# led-cube.net
KiCad netlist of a schematic drawn in Altium Designer
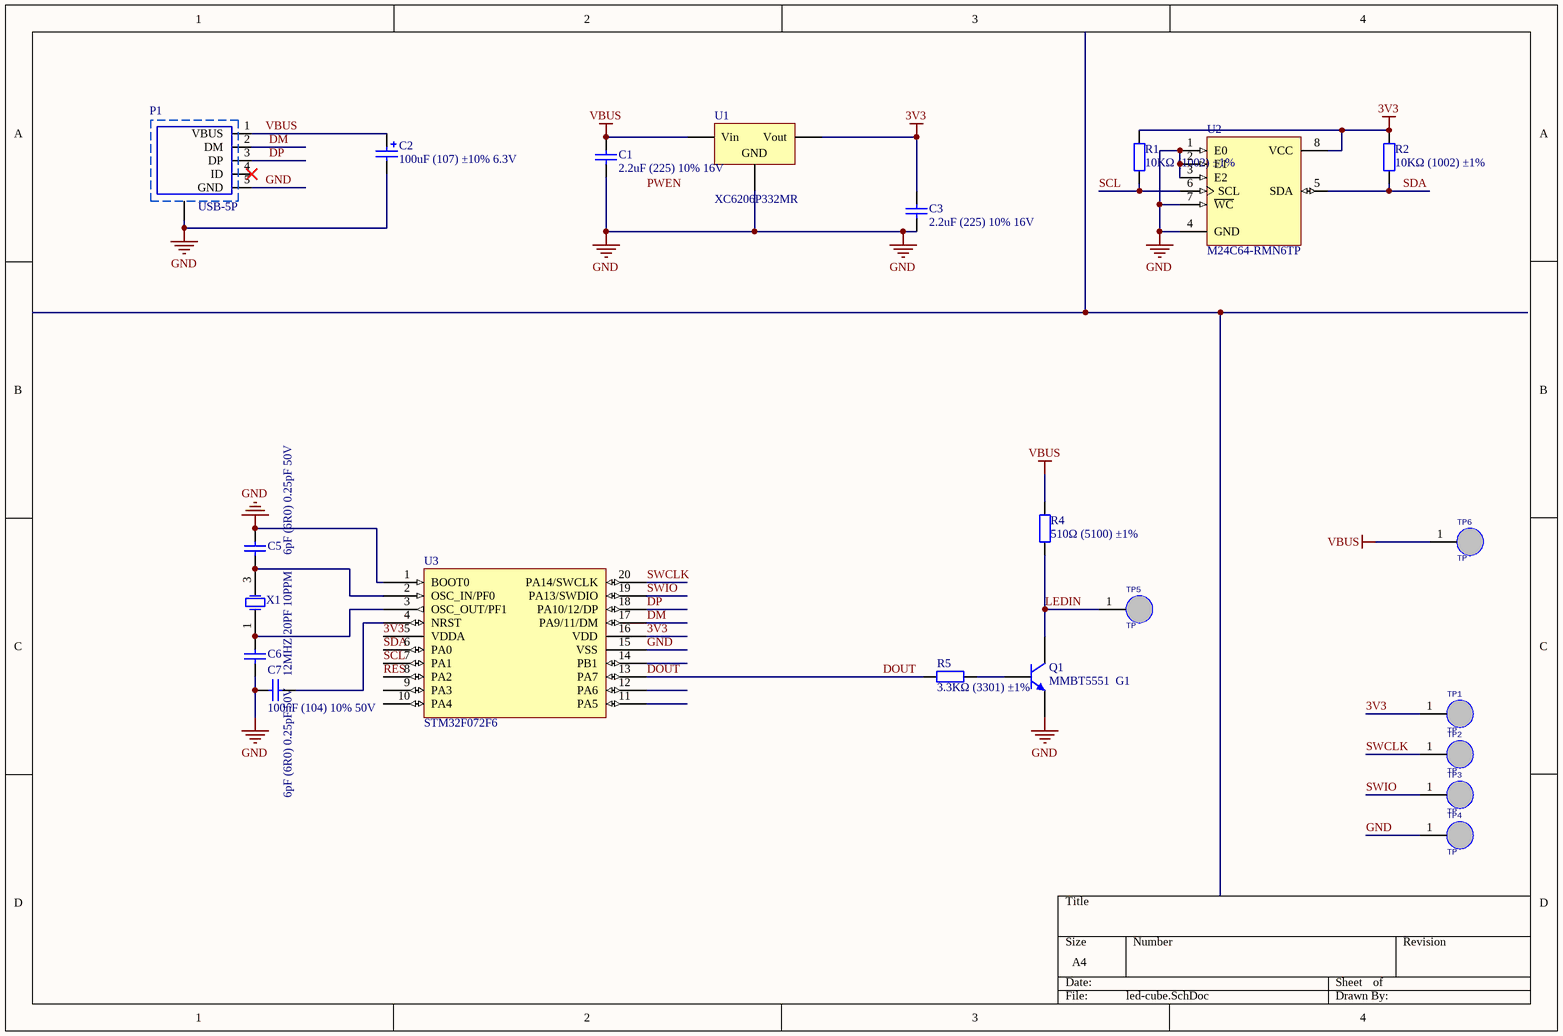
[diagram p0: led-cube.SchDoc]

(export (version "E")
  (design (tool "Eeschema 10.0.6"))
  (components
    (comp (ref "C1")
      (value "2.2uF (225) 10% 16V")
      (footprint "LC-0603_C")
      (description "贴片电容")
      (libsource (lib "Miscellaneous Devices LC") (part "0603 2.2uF (225) 10% 16V"))
    )
    (comp (ref "C2")
      (value "100uF (107) ±10% 6.3V")
      (footprint "LC-CASE-B_3528")
      (description "钽电容")
      (libsource (lib "Miscellaneous Devices LC") (part "3528 100uF (107) 10% 6.3V"))
    )
    (comp (ref "C3")
      (value "2.2uF (225) 10% 16V")
      (footprint "LC-0603_C")
      (description "贴片电容")
      (libsource (lib "Miscellaneous Devices LC") (part "0603 2.2uF (225) 10% 16V"))
    )
    (comp (ref "C5")
      (value "6pF (6R0) 0.25pF 50V")
      (footprint "LC-0603_C")
      (description "贴片电容")
      (libsource (lib "Miscellaneous Devices LC") (part "0603 6pF (6R0) 0.25pF 50V"))
    )
    (comp (ref "C6")
      (value "6pF (6R0) 0.25pF 50V")
      (footprint "LC-0603_C")
      (description "贴片电容")
      (libsource (lib "Miscellaneous Devices LC") (part "0603 6pF (6R0) 0.25pF 50V"))
    )
    (comp (ref "C7")
      (value "100nF (104) 10% 50V")
      (footprint "LC-0603_C")
      (description "贴片电容")
      (libsource (lib "Miscellaneous Devices LC") (part "0603 100nF (104) 10% 50V"))
    )
    (comp (ref "P1") (value "USB-5P") (footprint "USBMICRO-5P") (libsource (lib "tony") (part "USB-5P")))
    (comp (ref "Q1")
      (value "MMBT5551  G1")
      (footprint "LC-SOT-23(SOT-23-3)")
      (description "三极管")
      (libsource (lib "Miscellaneous Devices LC") (part "SOT-23 MMBT5551  G1"))
    )
    (comp (ref "R1")
      (value "10KΩ (1002) ±1%")
      (footprint "LC-0603_R")
      (description "贴片电阻")
      (libsource (lib "Miscellaneous Devices LC") (part "0603 10KΩ (1002) 1%"))
    )
    (comp (ref "R2")
      (value "10KΩ (1002) ±1%")
      (footprint "LC-0603_R")
      (description "贴片电阻")
      (libsource (lib "Miscellaneous Devices LC") (part "0603 10KΩ (1002) 1%"))
    )
    (comp (ref "R4")
      (value "510Ω (5100) ±1%")
      (footprint "LC-0603_R")
      (description "贴片电阻")
      (libsource (lib "Miscellaneous Devices LC") (part "0603 510Ω (5100) 1%"))
    )
    (comp (ref "R5")
      (value "3.3KΩ (3301) ±1%")
      (footprint "LC-0603_R")
      (description "贴片电阻")
      (libsource (lib "Miscellaneous Devices LC") (part "0603 3.3KΩ (3301) 1%"))
    )
    (comp (ref "TP1")
      (value "TP")
      (footprint "TestPoint")
      (description "测试点")
      (libsource (lib "tony") (part "TP"))
    )
    (comp (ref "TP2")
      (value "TP")
      (footprint "TestPoint")
      (description "测试点")
      (libsource (lib "tony") (part "TP"))
    )
    (comp (ref "TP3")
      (value "TP")
      (footprint "TestPoint")
      (description "测试点")
      (libsource (lib "tony") (part "TP"))
    )
    (comp (ref "TP4")
      (value "TP")
      (footprint "TestPoint")
      (description "测试点")
      (libsource (lib "tony") (part "TP"))
    )
    (comp (ref "TP5")
      (value "TP")
      (footprint "TestPoint")
      (description "测试点")
      (libsource (lib "tony") (part "TP"))
    )
    (comp (ref "TP6")
      (value "TP")
      (footprint "TestPoint")
      (description "测试点")
      (libsource (lib "tony") (part "TP"))
    )
    (comp (ref "U1")
      (value "XC6206P332MR")
      (footprint "LC-SOT-23-3L")
      (description "低压差线性稳压(LDO)")
      (libsource (lib "Miscellaneous Devices LC") (part "SOT-23 XC6206P332MR"))
    )
    (comp (ref "U2")
      (value "M24C64-RMN6TP")
      (footprint "LC-SOIC-8_150mil")
      (description "EEPROM")
      (libsource (lib "Miscellaneous Devices LC") (part "M24C64-RMN6TP"))
    )
    (comp (ref "U3")
      (value "STM32F072F6")
      (footprint "TSSOP20")
      (libsource (lib "tony") (part "STM32F072F6"))
    )
    (comp (ref "X1")
      (value "12MHZ 20PF 10PPM")
      (footprint "LC-SMD-3225_4P")
      (description "贴片晶振")
      (libsource (lib "Miscellaneous Devices LC") (part "SMD-3225_4P  12MHZ 20PF 10PPM"))
    )
  )
  (nets
    (net (code "1") (name "/DM") (class "Default")
      (node (ref "P1") (pin "2") (pinfunction "DM_2") (pintype "passive"))
      (node (ref "U3") (pin "17") (pinfunction "PA9/11/DM_17") (pintype "bidirectional"))
    )
    (net (code "2") (name "/DOUT") (class "Default")
      (node (ref "R5") (pin "1") (pinfunction "1_1") (pintype "passive"))
      (node (ref "U3") (pin "13") (pinfunction "PA7_13") (pintype "bidirectional"))
    )
    (net (code "3") (name "/DP") (class "Default")
      (node (ref "P1") (pin "3") (pinfunction "DP_3") (pintype "passive"))
      (node (ref "U3") (pin "18") (pinfunction "PA10/12/DP_18") (pintype "bidirectional"))
    )
    (net (code "4") (name "/LEDIN") (class "Default")
      (node (ref "Q1") (pin "3") (pinfunction "C_3") (pintype "passive"))
      (node (ref "R4") (pin "1") (pinfunction "1_1") (pintype "passive"))
      (node (ref "TP5") (pin "1") (pintype "passive"))
    )
    (net (code "6") (name "/RES") (class "Default")
      (node (ref "U3") (pin "8") (pinfunction "PA2_8") (pintype "bidirectional"))
    )
    (net (code "7") (name "/SCL") (class "Default")
      (node (ref "R1") (pin "2") (pinfunction "2_2") (pintype "passive"))
      (node (ref "U2") (pin "6") (pinfunction "SCL_6") (pintype "input"))
      (node (ref "U3") (pin "7") (pinfunction "PA1_7") (pintype "bidirectional"))
    )
    (net (code "8") (name "/SDA") (class "Default")
      (node (ref "R2") (pin "2") (pinfunction "2_2") (pintype "passive"))
      (node (ref "U2") (pin "5") (pinfunction "SDA_5") (pintype "bidirectional"))
      (node (ref "U3") (pin "6") (pinfunction "PA0_6") (pintype "bidirectional"))
    )
    (net (code "9") (name "/SWCLK") (class "Default")
      (node (ref "TP2") (pin "1") (pintype "passive"))
      (node (ref "U3") (pin "20") (pinfunction "PA14/SWCLK_20") (pintype "bidirectional"))
    )
    (net (code "10") (name "/SWIO") (class "Default")
      (node (ref "TP3") (pin "1") (pintype "passive"))
      (node (ref "U3") (pin "19") (pinfunction "PA13/SWDIO_19") (pintype "bidirectional"))
    )
    (net (code "11") (name "3V3") (class "Default")
      (node (ref "C3") (pin "2") (pinfunction "2_2") (pintype "passive"))
      (node (ref "R1") (pin "1") (pinfunction "1_1") (pintype "passive"))
      (node (ref "R2") (pin "1") (pinfunction "1_1") (pintype "passive"))
      (node (ref "TP1") (pin "1") (pintype "passive"))
      (node (ref "U1") (pin "2") (pinfunction "Vout_2") (pintype "passive"))
      (node (ref "U2") (pin "8") (pinfunction "VCC_8") (pintype "power_in"))
      (node (ref "U3") (pin "16") (pinfunction "VDD_16") (pintype "power_in"))
      (node (ref "U3") (pin "5") (pinfunction "VDDA_5") (pintype "power_in"))
    )
    (net (code "12") (name "GND") (class "Default")
      (node (ref "C1") (pin "1") (pinfunction "1_1") (pintype "passive"))
      (node (ref "C2") (pin "2") (pinfunction "2_2") (pintype "passive"))
      (node (ref "C3") (pin "1") (pinfunction "1_1") (pintype "passive"))
      (node (ref "C5") (pin "1") (pinfunction "1_1") (pintype "passive"))
      (node (ref "C6") (pin "2") (pinfunction "2_2") (pintype "passive"))
      (node (ref "C7") (pin "2") (pinfunction "2_2") (pintype "passive"))
      (node (ref "P1") (pin "5") (pinfunction "GND_5") (pintype "passive"))
      (node (ref "P1") (pin "Shell") (pintype "passive"))
      (node (ref "Q1") (pin "2") (pinfunction "E_2") (pintype "passive"))
      (node (ref "TP4") (pin "1") (pintype "passive"))
      (node (ref "U1") (pin "1") (pinfunction "GND_1") (pintype "passive"))
      (node (ref "U2") (pin "1") (pinfunction "E0_1") (pintype "input"))
      (node (ref "U2") (pin "2") (pinfunction "E1_2") (pintype "input"))
      (node (ref "U2") (pin "3") (pinfunction "E2_3") (pintype "input"))
      (node (ref "U2") (pin "4") (pinfunction "GND_4") (pintype "power_in"))
      (node (ref "U2") (pin "7") (pinfunction "~{WC}_7") (pintype "input"))
      (node (ref "U3") (pin "1") (pinfunction "BOOT0_1") (pintype "input"))
      (node (ref "U3") (pin "15") (pinfunction "VSS_15") (pintype "power_in"))
    )
    (net (code "13") (name "Net-(Q1-B)") (class "Default")
      (node (ref "Q1") (pin "1") (pinfunction "B_1") (pintype "passive"))
      (node (ref "R5") (pin "2") (pinfunction "2_2") (pintype "passive"))
    )
    (net (code "14") (name "Net-(U3-NRST)") (class "Default")
      (node (ref "C7") (pin "1") (pinfunction "1_1") (pintype "passive"))
      (node (ref "U3") (pin "4") (pinfunction "NRST_4") (pintype "bidirectional"))
    )
    (net (code "15") (name "Net-(U3-OSC_IN{slash}PF0)") (class "Default")
      (node (ref "C5") (pin "2") (pinfunction "2_2") (pintype "passive"))
      (node (ref "U3") (pin "2") (pinfunction "OSC_IN/PF0_2") (pintype "input"))
      (node (ref "X1") (pin "3") (pinfunction "OSC2_3") (pintype "passive"))
    )
    (net (code "16") (name "Net-(U3-OSC_OUT{slash}PF1)") (class "Default")
      (node (ref "C6") (pin "1") (pinfunction "1_1") (pintype "passive"))
      (node (ref "U3") (pin "3") (pinfunction "OSC_OUT/PF1_3") (pintype "output"))
      (node (ref "X1") (pin "1") (pinfunction "OSC1_1") (pintype "passive"))
    )
    (net (code "17") (name "VBUS") (class "Default")
      (node (ref "C1") (pin "2") (pinfunction "2_2") (pintype "passive"))
      (node (ref "C2") (pin "1") (pinfunction "1_1") (pintype "passive"))
      (node (ref "P1") (pin "1") (pinfunction "VBUS_1") (pintype "passive"))
      (node (ref "R4") (pin "2") (pinfunction "2_2") (pintype "passive"))
      (node (ref "TP6") (pin "1") (pintype "passive"))
      (node (ref "U1") (pin "3") (pinfunction "Vin_3") (pintype "passive"))
    )
    (net (code "18") (name "unconnected-(P1-ID-Pad4)") (class "Default")
      (node (ref "P1") (pin "4") (pinfunction "ID_4") (pintype "passive+no_connect"))
    )
    (net (code "19") (name "unconnected-(U3-PA3-Pad9)") (class "Default")
      (node (ref "U3") (pin "9") (pinfunction "PA3_9") (pintype "bidirectional"))
    )
    (net (code "20") (name "unconnected-(U3-PA4-Pad10)") (class "Default")
      (node (ref "U3") (pin "10") (pinfunction "PA4_10") (pintype "bidirectional"))
    )
    (net (code "21") (name "unconnected-(U3-PA5-Pad11)") (class "Default")
      (node (ref "U3") (pin "11") (pinfunction "PA5_11") (pintype "bidirectional"))
    )
    (net (code "22") (name "unconnected-(U3-PA6-Pad12)") (class "Default")
      (node (ref "U3") (pin "12") (pinfunction "PA6_12") (pintype "bidirectional"))
    )
    (net (code "23") (name "unconnected-(U3-PB1-Pad14)") (class "Default")
      (node (ref "U3") (pin "14") (pinfunction "PB1_14") (pintype "bidirectional"))
    )
  )
)
